# Carolo_schaltplan.net
KiCad netlist of a schematic drawn in EAGLE
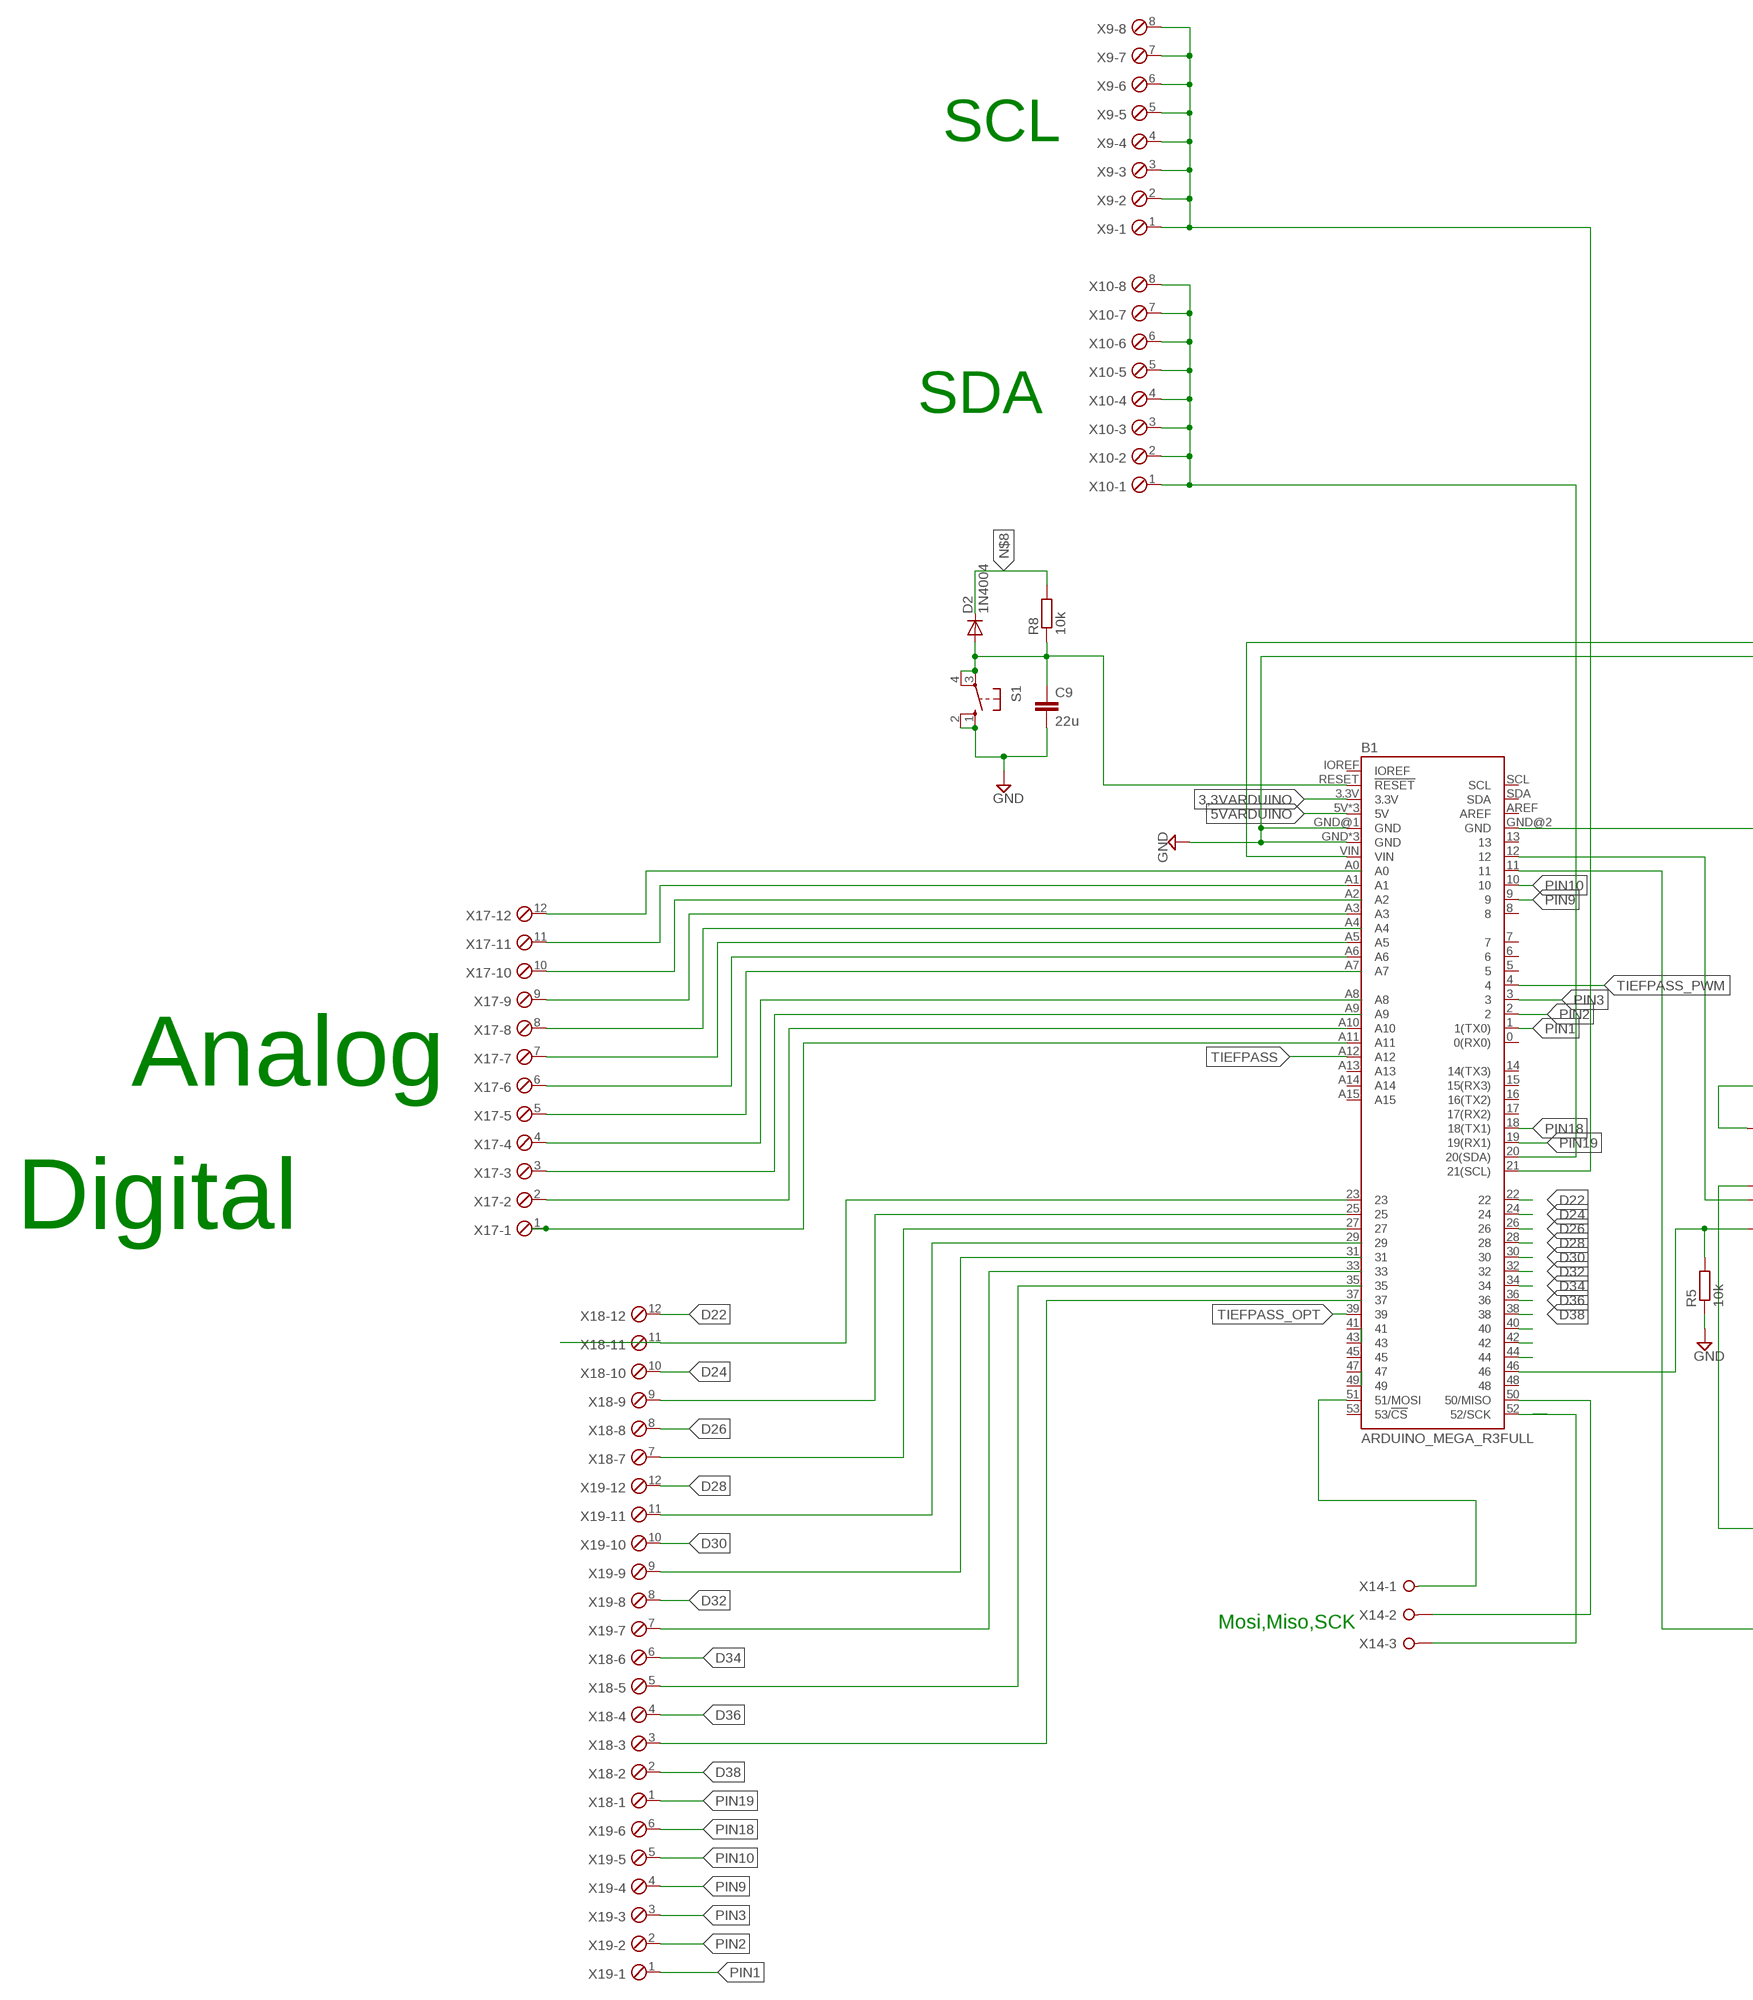
[diagram p0: schematic, sheet 1, part 1 of 2]
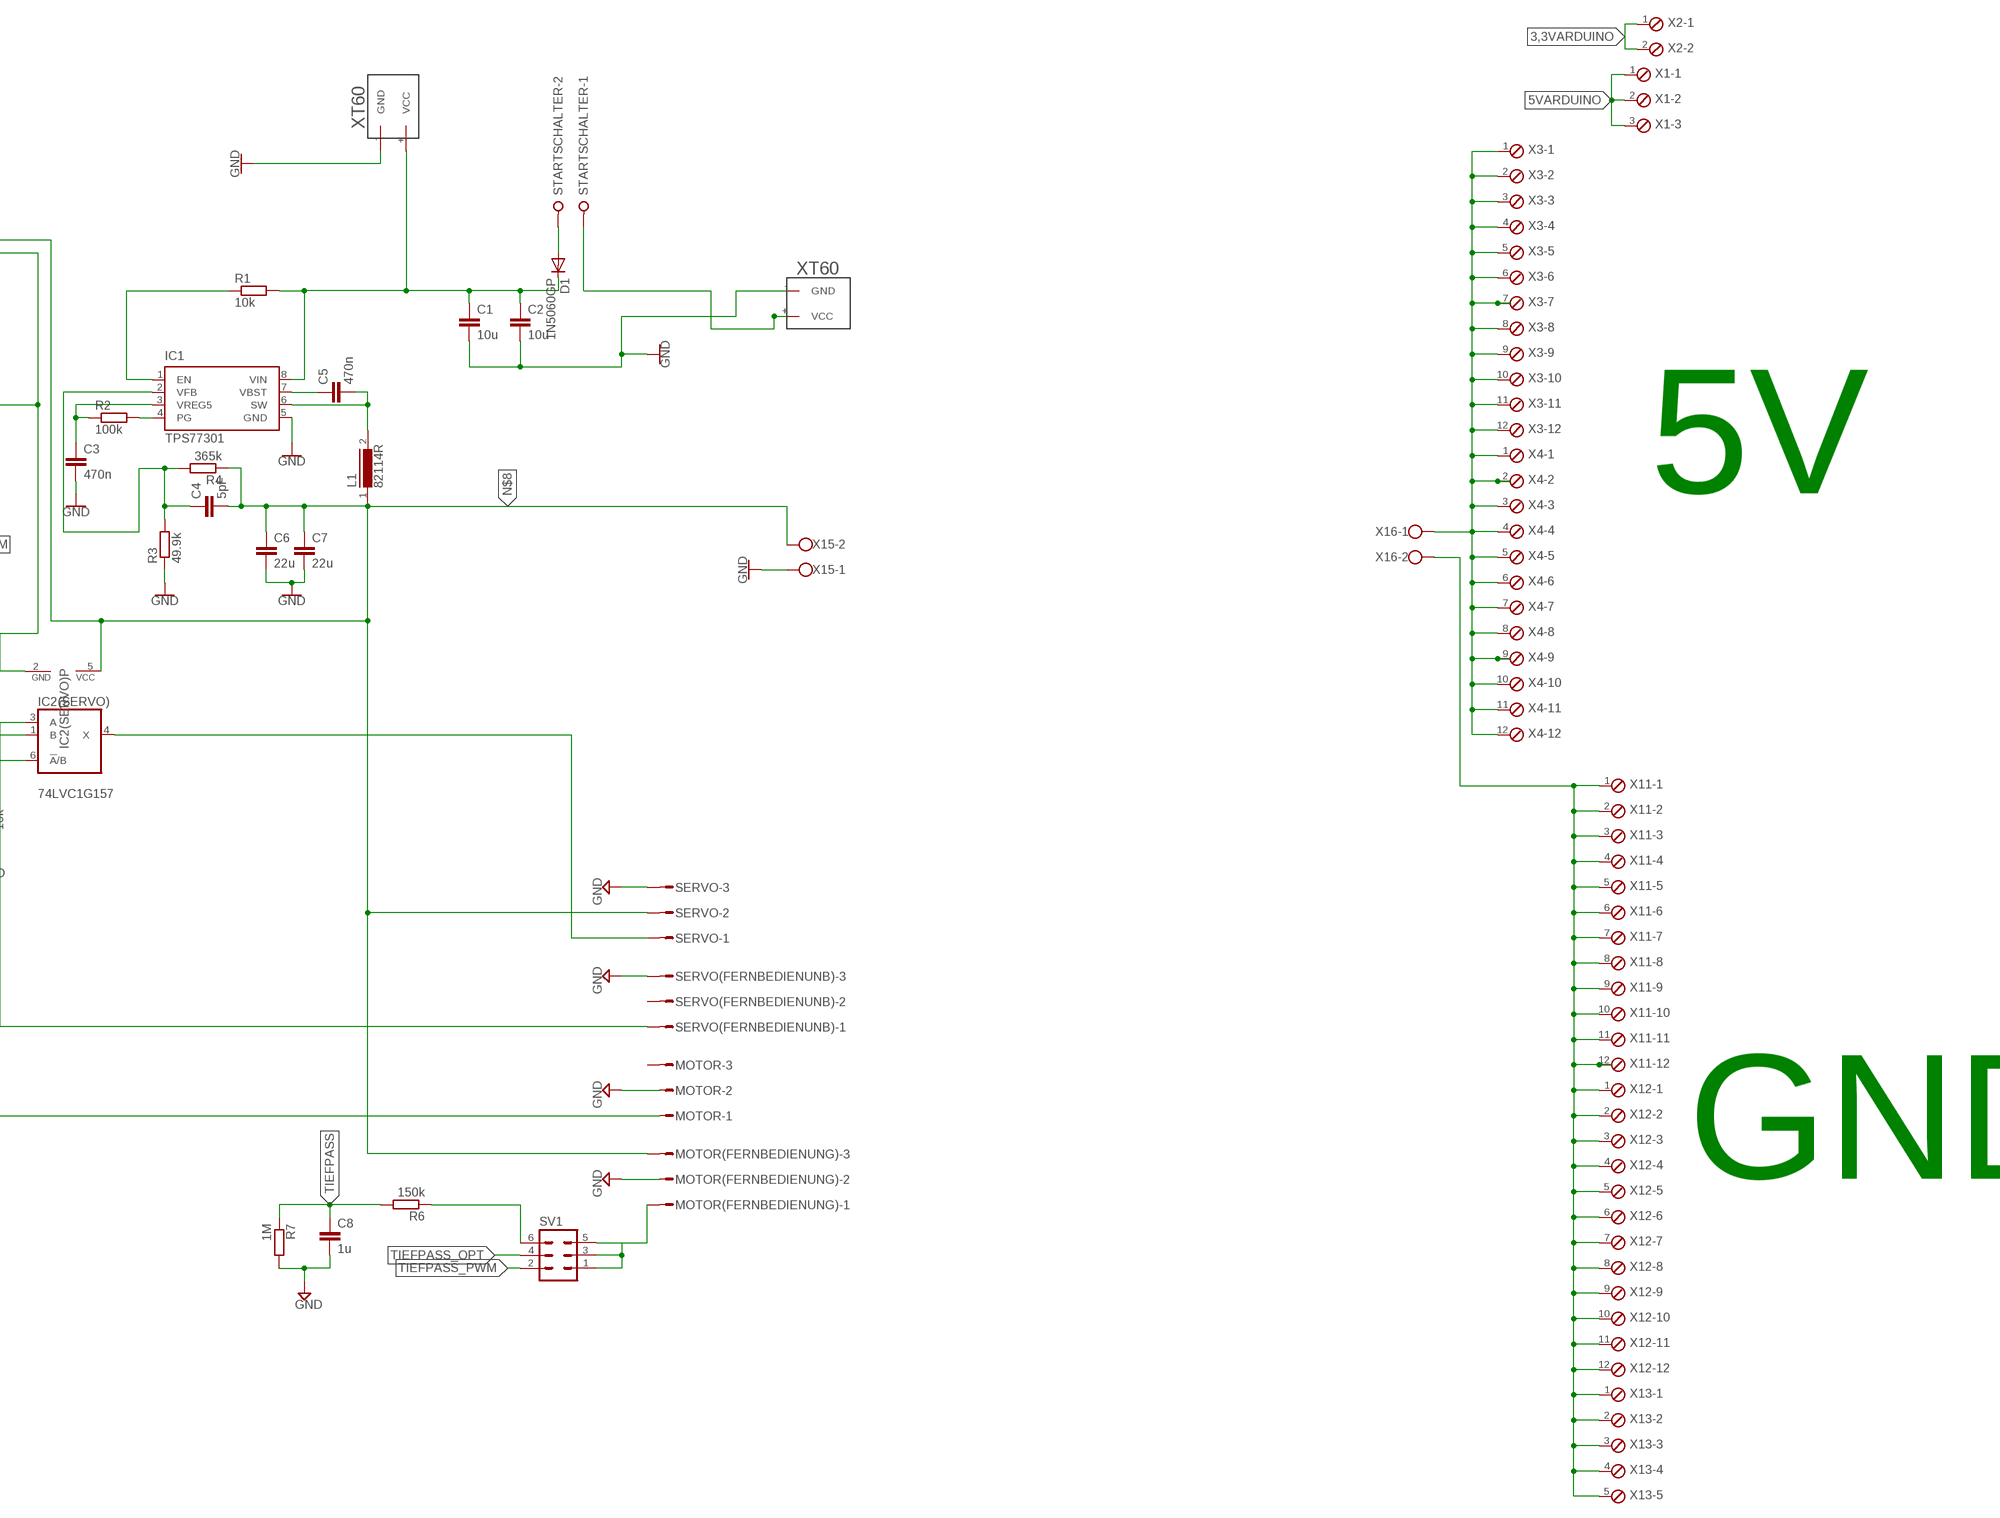
[diagram p1: schematic, sheet 1, part 2 of 2]

(export (version "E")
  (design (tool "Eeschema 10.0.6"))
  (components
    (comp (ref "B1")
      (value "ARDUINO_MEGA_R3FULL")
      (footprint "eagle-import:ARDUINO_MEGA_NO_SILK")
      (libsource (lib "eagle-import") (part "ARDUINO_MEGA_R3FULL"))
    )
    (comp (ref "C1")
      (value "10u")
      (footprint "eagle-import:C5B2.5")
      (libsource (lib "eagle-import") (part "C5/2.5"))
    )
    (comp (ref "C2")
      (value "10u")
      (footprint "eagle-import:C5B2.5")
      (libsource (lib "eagle-import") (part "C5/2.5"))
    )
    (comp (ref "C3")
      (value "470n")
      (footprint "eagle-import:C5B2.5")
      (libsource (lib "eagle-import") (part "C5/2.5"))
    )
    (comp (ref "C4")
      (value "5pF")
      (footprint "eagle-import:C5B2.5")
      (libsource (lib "eagle-import") (part "C5/2.5"))
    )
    (comp (ref "C5")
      (value "470n")
      (footprint "eagle-import:C5B2.5")
      (libsource (lib "eagle-import") (part "C5/2.5"))
    )
    (comp (ref "C6")
      (value "22u")
      (footprint "eagle-import:C5B2.5")
      (libsource (lib "eagle-import") (part "C5/2.5"))
    )
    (comp (ref "C7")
      (value "22u")
      (footprint "eagle-import:C5B2.5")
      (libsource (lib "eagle-import") (part "C5/2.5"))
    )
    (comp (ref "C8")
      (value "1u")
      (footprint "eagle-import:C5B2.5")
      (libsource (lib "eagle-import") (part "C5/2.5"))
    )
    (comp (ref "C9")
      (value "22u")
      (footprint "eagle-import:C5B2.5")
      (libsource (lib "eagle-import") (part "C5/2.5"))
    )
    (comp (ref "D1")
      (value "1N5060GP")
      (footprint "eagle-import:DO15-12")
      (libsource (lib "eagle-import") (part "1N5060GP"))
    )
    (comp (ref "D2")
      (value "1N4004")
      (footprint "eagle-import:DO41-10")
      (libsource (lib "eagle-import") (part "1N4004"))
    )
    (comp (ref "IC1")
      (value "TPS77301")
      (footprint "eagle-import:SOP-08")
      (fields (field (name "MF") "TEXAS INSTRUMENT CONNECTORS") (field (name "MPN") "TPS77301DGK"))
      (libsource (lib "eagle-import") (part "TPS77301"))
    )
    (comp (ref "IC2(SERVO)")
      (value "74LVC1G157")
      (footprint "eagle-import:DBV_R-PDSO-G6")
      (libsource (lib "eagle-import") (part "741G3157DBVR"))
    )
    (comp (ref "L1")
      (value "82114R")
      (footprint "eagle-import:82114R")
      (libsource (lib "eagle-import") (part "82114R"))
    )
    (comp (ref "MOTOR")
      (value "L03P")
      (footprint "eagle-import:L03P")
      (libsource (lib "eagle-import") (part "L03P"))
    )
    (comp (ref "MOTOR(FERNBEDIENUNG)")
      (value "L03P")
      (footprint "eagle-import:L03P")
      (libsource (lib "eagle-import") (part "L03P"))
    )
    (comp (ref "R1")
      (value "10k")
      (footprint "eagle-import:0309_12")
      (libsource (lib "eagle-import") (part "R-EU_0309/12"))
    )
    (comp (ref "R2")
      (value "100k")
      (footprint "eagle-import:0309_12")
      (libsource (lib "eagle-import") (part "R-EU_0309/12"))
    )
    (comp (ref "R3")
      (value "49.9k")
      (footprint "eagle-import:0309_12")
      (libsource (lib "eagle-import") (part "R-EU_0309/12"))
    )
    (comp (ref "R4")
      (value "365k")
      (footprint "eagle-import:0309_12")
      (libsource (lib "eagle-import") (part "R-EU_0309/12"))
    )
    (comp (ref "R5")
      (value "10k")
      (footprint "eagle-import:0309_12")
      (libsource (lib "eagle-import") (part "R-EU_0309/12"))
    )
    (comp (ref "R6")
      (value "150k")
      (footprint "eagle-import:0309_12")
      (libsource (lib "eagle-import") (part "R-EU_0309/12"))
    )
    (comp (ref "R7")
      (value "1M")
      (footprint "eagle-import:0309_12")
      (libsource (lib "eagle-import") (part "R-EU_0309/12"))
    )
    (comp (ref "R8")
      (value "10k")
      (footprint "eagle-import:0309_12")
      (libsource (lib "eagle-import") (part "R-EU_0309/12"))
    )
    (comp (ref "S1")
      (value "10-XX")
      (footprint "eagle-import:B3F-10XX")
      (fields (field (name "MPN") "B3F-1000"))
      (libsource (lib "eagle-import") (part "10-XX"))
    )
    (comp (ref "SERVO")
      (value "L03P")
      (footprint "eagle-import:L03P")
      (libsource (lib "eagle-import") (part "L03P"))
    )
    (comp (ref "SERVO(FERNBEDIENUNB)")
      (value "L03P")
      (footprint "eagle-import:L03P")
      (libsource (lib "eagle-import") (part "L03P"))
    )
    (comp (ref "STARTSCHALTER")
      (value "W237-02P")
      (footprint "eagle-import:W237-132")
      (libsource (lib "eagle-import") (part "W237-02P"))
    )
    (comp (ref "SV1")
      (value "ML6")
      (footprint "eagle-import:ML6")
      (libsource (lib "eagle-import") (part "ML6"))
    )
    (comp (ref "U$1")
      (value "XT60")
      (footprint "eagle-import:XT60")
      (libsource (lib "eagle-import") (part "XT60"))
    )
    (comp (ref "U$2")
      (value "XT60")
      (footprint "eagle-import:XT60")
      (libsource (lib "eagle-import") (part "XT60"))
    )
    (comp (ref "X1")
      (value "MPT3")
      (footprint "eagle-import:3POL254")
      (libsource (lib "eagle-import") (part "MPT3"))
    )
    (comp (ref "X2")
      (value "MPT2")
      (footprint "eagle-import:2POL254")
      (libsource (lib "eagle-import") (part "MPT2"))
    )
    (comp (ref "X3")
      (value "MPT12")
      (footprint "eagle-import:12POL254")
      (libsource (lib "eagle-import") (part "MPT12"))
    )
    (comp (ref "X4")
      (value "MPT12")
      (footprint "eagle-import:12POL254")
      (libsource (lib "eagle-import") (part "MPT12"))
    )
    (comp (ref "X9")
      (value "MPT8")
      (footprint "eagle-import:8POL254")
      (libsource (lib "eagle-import") (part "MPT8"))
    )
    (comp (ref "X10")
      (value "MPT8")
      (footprint "eagle-import:8POL254")
      (libsource (lib "eagle-import") (part "MPT8"))
    )
    (comp (ref "X11")
      (value "MPT12")
      (footprint "eagle-import:12POL254")
      (libsource (lib "eagle-import") (part "MPT12"))
    )
    (comp (ref "X12")
      (value "MPT12")
      (footprint "eagle-import:12POL254")
      (libsource (lib "eagle-import") (part "MPT12"))
    )
    (comp (ref "X13")
      (value "MPT5")
      (footprint "eagle-import:5POL254")
      (libsource (lib "eagle-import") (part "MPT5"))
    )
    (comp (ref "X14")
      (value "W237-03P")
      (footprint "eagle-import:W237-133")
      (libsource (lib "eagle-import") (part "W237-03P"))
    )
    (comp (ref "X15")
      (value "W237-102")
      (footprint "eagle-import:W237-102")
      (fields (field (name "MPN") "237-102"))
      (libsource (lib "eagle-import") (part "W237-102"))
    )
    (comp (ref "X16")
      (value "W237-102")
      (footprint "eagle-import:W237-102")
      (fields (field (name "MPN") "237-102"))
      (libsource (lib "eagle-import") (part "W237-102"))
    )
    (comp (ref "X17")
      (value "MPT12")
      (footprint "eagle-import:12POL254")
      (libsource (lib "eagle-import") (part "MPT12"))
    )
    (comp (ref "X18")
      (value "MPT12")
      (footprint "eagle-import:12POL254")
      (libsource (lib "eagle-import") (part "MPT12"))
    )
    (comp (ref "X19")
      (value "MPT12")
      (footprint "eagle-import:12POL254")
      (libsource (lib "eagle-import") (part "MPT12"))
    )
  )
  (nets
    (net (code "1") (name "3,3VARDUINO") (class "Default")
      (node (ref "B1") (pin "3.3V") (pinfunction "3.3V_3.3V") (pintype "bidirectional"))
      (node (ref "X2") (pin "1") (pinfunction "1_1") (pintype "passive"))
      (node (ref "X2") (pin "2") (pinfunction "1_2") (pintype "passive"))
    )
    (net (code "2") (name "5VARDUINO") (class "Default")
      (node (ref "B1") (pin "5V") (pinfunction "5V_5V") (pintype "bidirectional"))
      (node (ref "B1") (pin "5V@1") (pinfunction "5V_5V@1") (pintype "bidirectional"))
      (node (ref "B1") (pin "5V@2") (pinfunction "5V_5V@2") (pintype "bidirectional"))
      (node (ref "X1") (pin "1") (pinfunction "1_1") (pintype "passive"))
      (node (ref "X1") (pin "2") (pinfunction "1_2") (pintype "passive"))
      (node (ref "X1") (pin "3") (pinfunction "1_3") (pintype "passive"))
    )
    (net (code "3") (name "D22") (class "Default")
      (node (ref "B1") (pin "22") (pinfunction "22_22") (pintype "bidirectional"))
      (node (ref "X18") (pin "12") (pinfunction "1_12") (pintype "passive"))
    )
    (net (code "4") (name "D24") (class "Default")
      (node (ref "B1") (pin "24") (pinfunction "24_24") (pintype "bidirectional"))
      (node (ref "X18") (pin "10") (pinfunction "1_10") (pintype "passive"))
    )
    (net (code "5") (name "D26") (class "Default")
      (node (ref "B1") (pin "26") (pinfunction "26_26") (pintype "bidirectional"))
      (node (ref "X18") (pin "8") (pinfunction "1_8") (pintype "passive"))
    )
    (net (code "6") (name "D28") (class "Default")
      (node (ref "B1") (pin "28") (pinfunction "28_28") (pintype "bidirectional"))
      (node (ref "X19") (pin "12") (pinfunction "1_12") (pintype "passive"))
    )
    (net (code "7") (name "D30") (class "Default")
      (node (ref "B1") (pin "30") (pinfunction "30_30") (pintype "bidirectional"))
      (node (ref "X19") (pin "10") (pinfunction "1_10") (pintype "passive"))
    )
    (net (code "8") (name "D32") (class "Default")
      (node (ref "B1") (pin "32") (pinfunction "32_32") (pintype "bidirectional"))
      (node (ref "X19") (pin "8") (pinfunction "1_8") (pintype "passive"))
    )
    (net (code "9") (name "D34") (class "Default")
      (node (ref "B1") (pin "34") (pinfunction "34_34") (pintype "bidirectional"))
      (node (ref "X18") (pin "6") (pinfunction "1_6") (pintype "passive"))
    )
    (net (code "10") (name "D36") (class "Default")
      (node (ref "B1") (pin "36") (pinfunction "36_36") (pintype "bidirectional"))
      (node (ref "X18") (pin "4") (pinfunction "1_4") (pintype "passive"))
    )
    (net (code "11") (name "D38") (class "Default")
      (node (ref "B1") (pin "38") (pinfunction "38_38") (pintype "bidirectional"))
      (node (ref "X18") (pin "2") (pinfunction "1_2") (pintype "passive"))
    )
    (net (code "12") (name "GND") (class "Default")
      (node (ref "B1") (pin "GND") (pinfunction "GND_GND") (pintype "bidirectional"))
      (node (ref "B1") (pin "GND@1") (pinfunction "GND_GND@1") (pintype "bidirectional"))
      (node (ref "B1") (pin "GND@2") (pinfunction "GND_GND@2") (pintype "bidirectional"))
      (node (ref "B1") (pin "GND@3") (pinfunction "GND_GND@3") (pintype "bidirectional"))
      (node (ref "B1") (pin "GND@4") (pinfunction "GND_GND@4") (pintype "bidirectional"))
      (node (ref "C1") (pin "2") (pinfunction "2_2") (pintype "passive"))
      (node (ref "C2") (pin "2") (pinfunction "2_2") (pintype "passive"))
      (node (ref "C3") (pin "2") (pinfunction "2_2") (pintype "passive"))
      (node (ref "C6") (pin "2") (pinfunction "2_2") (pintype "passive"))
      (node (ref "C7") (pin "2") (pinfunction "2_2") (pintype "passive"))
      (node (ref "C8") (pin "2") (pinfunction "2_2") (pintype "passive"))
      (node (ref "C9") (pin "2") (pinfunction "2_2") (pintype "passive"))
      (node (ref "IC1") (pin "5") (pinfunction "GND_5") (pintype "input"))
      (node (ref "IC2(SERVO)") (pin "2") (pinfunction "GND_2") (pintype "power_in"))
      (node (ref "R3") (pin "1") (pinfunction "1_1") (pintype "passive"))
      (node (ref "R5") (pin "1") (pinfunction "1_1") (pintype "passive"))
      (node (ref "R7") (pin "2") (pinfunction "2_2") (pintype "passive"))
      (node (ref "S1") (pin "1") (pinfunction "S_1") (pintype "passive"))
      (node (ref "S1") (pin "2") (pinfunction "S1_2") (pintype "passive"))
      (node (ref "SERVO") (pin "3") (pinfunction "S_3") (pintype "passive"))
      (node (ref "SERVO(FERNBEDIENUNB)") (pin "3") (pinfunction "S_3") (pintype "passive"))
      (node (ref "U$2") (pin "-") (pinfunction "GND_-") (pintype "bidirectional"))
      (node (ref "X15") (pin "1") (pinfunction "KL_1") (pintype "passive"))
    )
    (net (code "13") (name "N$8") (class "Default")
      (node (ref "B1") (pin "VIN") (pinfunction "VIN_VIN") (pintype "bidirectional"))
      (node (ref "C4") (pin "2") (pinfunction "2_2") (pintype "passive"))
      (node (ref "C6") (pin "1") (pinfunction "1_1") (pintype "passive"))
      (node (ref "C7") (pin "1") (pinfunction "1_1") (pintype "passive"))
      (node (ref "D2") (pin "C") (pinfunction "C_C") (pintype "passive"))
      (node (ref "IC2(SERVO)") (pin "5") (pinfunction "VCC_5") (pintype "power_in"))
      (node (ref "L1") (pin "1") (pinfunction "1_1") (pintype "passive"))
      (node (ref "MOTOR(FERNBEDIENUNG)") (pin "3") (pinfunction "S_3") (pintype "passive"))
      (node (ref "R4") (pin "1") (pinfunction "1_1") (pintype "passive"))
      (node (ref "R8") (pin "2") (pinfunction "2_2") (pintype "passive"))
      (node (ref "SERVO") (pin "2") (pinfunction "S_2") (pintype "passive"))
      (node (ref "X15") (pin "2") (pinfunction "KL_2") (pintype "passive"))
      (node (ref "X16") (pin "1") (pinfunction "KL_1") (pintype "passive"))
      (node (ref "X3") (pin "1") (pinfunction "1_1") (pintype "passive"))
      (node (ref "X3") (pin "10") (pinfunction "1_10") (pintype "passive"))
      (node (ref "X3") (pin "11") (pinfunction "1_11") (pintype "passive"))
      (node (ref "X3") (pin "12") (pinfunction "1_12") (pintype "passive"))
      (node (ref "X3") (pin "2") (pinfunction "1_2") (pintype "passive"))
      (node (ref "X3") (pin "3") (pinfunction "1_3") (pintype "passive"))
      (node (ref "X3") (pin "4") (pinfunction "1_4") (pintype "passive"))
      (node (ref "X3") (pin "5") (pinfunction "1_5") (pintype "passive"))
      (node (ref "X3") (pin "6") (pinfunction "1_6") (pintype "passive"))
      (node (ref "X3") (pin "7") (pinfunction "1_7") (pintype "passive"))
      (node (ref "X3") (pin "8") (pinfunction "1_8") (pintype "passive"))
      (node (ref "X3") (pin "9") (pinfunction "1_9") (pintype "passive"))
      (node (ref "X4") (pin "1") (pinfunction "1_1") (pintype "passive"))
      (node (ref "X4") (pin "10") (pinfunction "1_10") (pintype "passive"))
      (node (ref "X4") (pin "11") (pinfunction "1_11") (pintype "passive"))
      (node (ref "X4") (pin "12") (pinfunction "1_12") (pintype "passive"))
      (node (ref "X4") (pin "2") (pinfunction "1_2") (pintype "passive"))
      (node (ref "X4") (pin "3") (pinfunction "1_3") (pintype "passive"))
      (node (ref "X4") (pin "4") (pinfunction "1_4") (pintype "passive"))
      (node (ref "X4") (pin "5") (pinfunction "1_5") (pintype "passive"))
      (node (ref "X4") (pin "6") (pinfunction "1_6") (pintype "passive"))
      (node (ref "X4") (pin "7") (pinfunction "1_7") (pintype "passive"))
      (node (ref "X4") (pin "8") (pinfunction "1_8") (pintype "passive"))
      (node (ref "X4") (pin "9") (pinfunction "1_9") (pintype "passive"))
    )
    (net (code "14") (name "Net-(B1-20(SDA))") (class "Default")
      (node (ref "B1") (pin "20") (pinfunction "20(SDA)_20") (pintype "bidirectional"))
      (node (ref "X10") (pin "1") (pinfunction "1_1") (pintype "passive"))
      (node (ref "X10") (pin "2") (pinfunction "1_2") (pintype "passive"))
      (node (ref "X10") (pin "3") (pinfunction "1_3") (pintype "passive"))
      (node (ref "X10") (pin "4") (pinfunction "1_4") (pintype "passive"))
      (node (ref "X10") (pin "5") (pinfunction "1_5") (pintype "passive"))
      (node (ref "X10") (pin "6") (pinfunction "1_6") (pintype "passive"))
      (node (ref "X10") (pin "7") (pinfunction "1_7") (pintype "passive"))
      (node (ref "X10") (pin "8") (pinfunction "1_8") (pintype "passive"))
    )
    (net (code "15") (name "Net-(B1-21(SCL))") (class "Default")
      (node (ref "B1") (pin "21") (pinfunction "21(SCL)_21") (pintype "bidirectional"))
      (node (ref "X9") (pin "1") (pinfunction "1_1") (pintype "passive"))
      (node (ref "X9") (pin "2") (pinfunction "1_2") (pintype "passive"))
      (node (ref "X9") (pin "3") (pinfunction "1_3") (pintype "passive"))
      (node (ref "X9") (pin "4") (pinfunction "1_4") (pintype "passive"))
      (node (ref "X9") (pin "5") (pinfunction "1_5") (pintype "passive"))
      (node (ref "X9") (pin "6") (pinfunction "1_6") (pintype "passive"))
      (node (ref "X9") (pin "7") (pinfunction "1_7") (pintype "passive"))
      (node (ref "X9") (pin "8") (pinfunction "1_8") (pintype "passive"))
    )
    (net (code "16") (name "Net-(B1-50{slash}MISO)") (class "Default")
      (node (ref "B1") (pin "50") (pinfunction "50/MISO_50") (pintype "bidirectional"))
      (node (ref "X14") (pin "2") (pinfunction "KL_2") (pintype "passive"))
    )
    (net (code "17") (name "Net-(B1-52{slash}SCK)") (class "Default")
      (node (ref "B1") (pin "52") (pinfunction "52/SCK_52") (pintype "bidirectional"))
      (node (ref "X14") (pin "3") (pinfunction "KL_3") (pintype "passive"))
    )
    (net (code "18") (name "Net-(B1-PadA11)") (class "Default")
      (node (ref "B1") (pin "A11") (pinfunction "A11_A11") (pintype "bidirectional"))
      (node (ref "X17") (pin "1") (pinfunction "1_1") (pintype "passive"))
    )
    (net (code "19") (name "Net-(B1-~{RESET})") (class "Default")
      (node (ref "B1") (pin "RESET") (pinfunction "~{RESET}_RESET") (pintype "bidirectional"))
      (node (ref "C9") (pin "1") (pinfunction "1_1") (pintype "passive"))
      (node (ref "D2") (pin "A") (pinfunction "A_A") (pintype "passive"))
      (node (ref "R8") (pin "1") (pinfunction "1_1") (pintype "passive"))
      (node (ref "S1") (pin "3") (pinfunction "P_3") (pintype "passive"))
      (node (ref "S1") (pin "4") (pinfunction "P1_4") (pintype "passive"))
    )
    (net (code "20") (name "Net-(IC1-EN)") (class "Default")
      (node (ref "IC1") (pin "1") (pinfunction "EN_1") (pintype "input"))
      (node (ref "R1") (pin "1") (pinfunction "1_1") (pintype "passive"))
    )
    (net (code "21") (name "Net-(IC1-PG)") (class "Default")
      (node (ref "IC1") (pin "4") (pinfunction "PG_4") (pintype "power_in"))
      (node (ref "R2") (pin "2") (pinfunction "2_2") (pintype "passive"))
    )
    (net (code "22") (name "Net-(IC1-SW)") (class "Default")
      (node (ref "C5") (pin "2") (pinfunction "2_2") (pintype "passive"))
      (node (ref "IC1") (pin "6") (pinfunction "SW_6") (pintype "input"))
      (node (ref "L1") (pin "2") (pinfunction "2_2") (pintype "passive"))
    )
    (net (code "23") (name "Net-(IC1-VBST)") (class "Default")
      (node (ref "C5") (pin "1") (pinfunction "1_1") (pintype "passive"))
      (node (ref "IC1") (pin "7") (pinfunction "VBST_7") (pintype "output"))
    )
    (net (code "24") (name "Net-(IC1-VFB)") (class "Default")
      (node (ref "C4") (pin "1") (pinfunction "1_1") (pintype "passive"))
      (node (ref "IC1") (pin "2") (pinfunction "VFB_2") (pintype "input"))
      (node (ref "R3") (pin "2") (pinfunction "2_2") (pintype "passive"))
      (node (ref "R4") (pin "2") (pinfunction "2_2") (pintype "passive"))
    )
    (net (code "25") (name "Net-(IC1-VIN)") (class "Default")
      (node (ref "C1") (pin "1") (pinfunction "1_1") (pintype "passive"))
      (node (ref "C2") (pin "1") (pinfunction "1_1") (pintype "passive"))
      (node (ref "D1") (pin "C") (pinfunction "C_C") (pintype "passive"))
      (node (ref "IC1") (pin "8") (pinfunction "VIN_8") (pintype "passive"))
      (node (ref "R1") (pin "2") (pinfunction "2_2") (pintype "passive"))
      (node (ref "U$2") (pin "+") (pinfunction "VCC_+") (pintype "bidirectional"))
    )
    (net (code "26") (name "Net-(IC1-VREG5)") (class "Default")
      (node (ref "C3") (pin "1") (pinfunction "1_1") (pintype "passive"))
      (node (ref "IC1") (pin "3") (pinfunction "VREG5_3") (pintype "input"))
      (node (ref "R2") (pin "1") (pinfunction "1_1") (pintype "passive"))
    )
    (net (code "27") (name "Net-(IC2(SERVO)A-A)") (class "Default")
      (node (ref "IC2(SERVO)") (pin "3") (pinfunction "A_3") (pintype "bidirectional"))
      (node (ref "SERVO(FERNBEDIENUNB)") (pin "1") (pinfunction "S_1") (pintype "passive"))
    )
    (net (code "28") (name "Net-(IC2(SERVO)A-B)") (class "Default")
      (node (ref "B1") (pin "12") (pinfunction "12_12") (pintype "bidirectional"))
      (node (ref "IC2(SERVO)") (pin "1") (pinfunction "B_1") (pintype "bidirectional"))
    )
    (net (code "29") (name "Net-(IC2(SERVO)A-X)") (class "Default")
      (node (ref "IC2(SERVO)") (pin "4") (pinfunction "X_4") (pintype "bidirectional"))
      (node (ref "SERVO") (pin "1") (pinfunction "S_1") (pintype "passive"))
    )
    (net (code "30") (name "Net-(IC2(SERVO)A-~{A}{slash}B)") (class "Default")
      (node (ref "B1") (pin "46") (pinfunction "46_46") (pintype "bidirectional"))
      (node (ref "IC2(SERVO)") (pin "6") (pinfunction "~{A}/B_6") (pintype "input"))
      (node (ref "R5") (pin "2") (pinfunction "2_2") (pintype "passive"))
    )
    (net (code "31") (name "Net-(MOTOR(FERNBEDIENUNG)A-S)") (class "Default")
      (node (ref "MOTOR(FERNBEDIENUNG)") (pin "1") (pinfunction "S_1") (pintype "passive"))
      (node (ref "SV1") (pin "1") (pinfunction "1_1") (pintype "passive"))
      (node (ref "SV1") (pin "3") (pinfunction "3_3") (pintype "passive"))
      (node (ref "SV1") (pin "5") (pinfunction "5_5") (pintype "passive"))
    )
    (net (code "32") (name "Net-(R6-Pad1)") (class "Default")
      (node (ref "R6") (pin "1") (pinfunction "1_1") (pintype "passive"))
      (node (ref "SV1") (pin "6") (pinfunction "6_6") (pintype "passive"))
    )
    (net (code "33") (name "Net-(STARTSCHALTERA-KL)") (class "Default")
      (node (ref "STARTSCHALTER") (pin "1") (pinfunction "KL_1") (pintype "passive"))
      (node (ref "U$1") (pin "+") (pinfunction "VCC_+") (pintype "bidirectional"))
    )
    (net (code "34") (name "Net-(STARTSCHALTERB-KL)") (class "Default")
      (node (ref "D1") (pin "A") (pinfunction "A_A") (pintype "passive"))
      (node (ref "STARTSCHALTER") (pin "2") (pinfunction "KL_2") (pintype "passive"))
    )
    (net (code "35") (name "Net-(X11B-1)") (class "Default")
      (node (ref "X11") (pin "1") (pinfunction "1_1") (pintype "passive"))
      (node (ref "X11") (pin "10") (pinfunction "1_10") (pintype "passive"))
      (node (ref "X11") (pin "11") (pinfunction "1_11") (pintype "passive"))
      (node (ref "X11") (pin "12") (pinfunction "1_12") (pintype "passive"))
      (node (ref "X11") (pin "2") (pinfunction "1_2") (pintype "passive"))
      (node (ref "X11") (pin "3") (pinfunction "1_3") (pintype "passive"))
      (node (ref "X11") (pin "4") (pinfunction "1_4") (pintype "passive"))
      (node (ref "X11") (pin "5") (pinfunction "1_5") (pintype "passive"))
      (node (ref "X11") (pin "6") (pinfunction "1_6") (pintype "passive"))
      (node (ref "X11") (pin "7") (pinfunction "1_7") (pintype "passive"))
      (node (ref "X11") (pin "8") (pinfunction "1_8") (pintype "passive"))
      (node (ref "X11") (pin "9") (pinfunction "1_9") (pintype "passive"))
      (node (ref "X12") (pin "1") (pinfunction "1_1") (pintype "passive"))
      (node (ref "X12") (pin "10") (pinfunction "1_10") (pintype "passive"))
      (node (ref "X12") (pin "11") (pinfunction "1_11") (pintype "passive"))
      (node (ref "X12") (pin "12") (pinfunction "1_12") (pintype "passive"))
      (node (ref "X12") (pin "2") (pinfunction "1_2") (pintype "passive"))
      (node (ref "X12") (pin "3") (pinfunction "1_3") (pintype "passive"))
      (node (ref "X12") (pin "4") (pinfunction "1_4") (pintype "passive"))
      (node (ref "X12") (pin "5") (pinfunction "1_5") (pintype "passive"))
      (node (ref "X12") (pin "6") (pinfunction "1_6") (pintype "passive"))
      (node (ref "X12") (pin "7") (pinfunction "1_7") (pintype "passive"))
      (node (ref "X12") (pin "8") (pinfunction "1_8") (pintype "passive"))
      (node (ref "X12") (pin "9") (pinfunction "1_9") (pintype "passive"))
      (node (ref "X13") (pin "1") (pinfunction "1_1") (pintype "passive"))
      (node (ref "X13") (pin "2") (pinfunction "1_2") (pintype "passive"))
      (node (ref "X13") (pin "3") (pinfunction "1_3") (pintype "passive"))
      (node (ref "X13") (pin "4") (pinfunction "1_4") (pintype "passive"))
      (node (ref "X13") (pin "5") (pinfunction "1_5") (pintype "passive"))
      (node (ref "X16") (pin "2") (pinfunction "KL_2") (pintype "passive"))
    )
    (net (code "36") (name "Net-(X17C-1)") (class "Default")
      (node (ref "B1") (pin "A1") (pinfunction "A1_A1") (pintype "bidirectional"))
      (node (ref "X17") (pin "11") (pinfunction "1_11") (pintype "passive"))
    )
    (net (code "37") (name "Net-(X17E-1)") (class "Default")
      (node (ref "B1") (pin "A10") (pinfunction "A10_A10") (pintype "bidirectional"))
      (node (ref "X17") (pin "2") (pinfunction "1_2") (pintype "passive"))
    )
    (net (code "38") (name "Net-(X17I-1)") (class "Default")
      (node (ref "B1") (pin "A6") (pinfunction "A6_A6") (pintype "bidirectional"))
      (node (ref "X17") (pin "6") (pinfunction "1_6") (pintype "passive"))
    )
    (net (code "39") (name "Net-(X17J-1)") (class "Default")
      (node (ref "B1") (pin "A5") (pinfunction "A5_A5") (pintype "bidirectional"))
      (node (ref "X17") (pin "7") (pinfunction "1_7") (pintype "passive"))
    )
    (net (code "40") (name "Net-(X17L-1)") (class "Default")
      (node (ref "B1") (pin "A3") (pinfunction "A3_A3") (pintype "bidirectional"))
      (node (ref "X17") (pin "9") (pinfunction "1_9") (pintype "passive"))
    )
    (net (code "41") (name "Net-(X18C-1)") (class "Default")
      (node (ref "B1") (pin "23") (pinfunction "23_23") (pintype "bidirectional"))
      (node (ref "X18") (pin "11") (pinfunction "1_11") (pintype "passive"))
    )
    (net (code "42") (name "Net-(X18J-1)") (class "Default")
      (node (ref "B1") (pin "27") (pinfunction "27_27") (pintype "bidirectional"))
      (node (ref "X18") (pin "7") (pinfunction "1_7") (pintype "passive"))
    )
    (net (code "43") (name "Net-(X18L-1)") (class "Default")
      (node (ref "B1") (pin "25") (pinfunction "25_25") (pintype "bidirectional"))
      (node (ref "X18") (pin "9") (pinfunction "1_9") (pintype "passive"))
    )
    (net (code "44") (name "PIN1") (class "Default")
      (node (ref "B1") (pin "1") (pinfunction "1(TX0)_1") (pintype "bidirectional"))
      (node (ref "X19") (pin "1") (pinfunction "1_1") (pintype "passive"))
    )
    (net (code "45") (name "PIN2") (class "Default")
      (node (ref "B1") (pin "2") (pinfunction "2_2") (pintype "bidirectional"))
      (node (ref "X19") (pin "2") (pinfunction "1_2") (pintype "passive"))
    )
    (net (code "46") (name "PIN3") (class "Default")
      (node (ref "B1") (pin "3") (pinfunction "3_3") (pintype "bidirectional"))
      (node (ref "X19") (pin "3") (pinfunction "1_3") (pintype "passive"))
    )
    (net (code "47") (name "PIN9") (class "Default")
      (node (ref "B1") (pin "9") (pinfunction "9_9") (pintype "bidirectional"))
      (node (ref "X19") (pin "4") (pinfunction "1_4") (pintype "passive"))
    )
    (net (code "48") (name "PIN10") (class "Default")
      (node (ref "B1") (pin "10") (pinfunction "10_10") (pintype "bidirectional"))
      (node (ref "X19") (pin "5") (pinfunction "1_5") (pintype "passive"))
    )
    (net (code "49") (name "PIN18") (class "Default")
      (node (ref "B1") (pin "18") (pinfunction "18(TX1)_18") (pintype "bidirectional"))
      (node (ref "X19") (pin "6") (pinfunction "1_6") (pintype "passive"))
    )
    (net (code "50") (name "PIN19") (class "Default")
      (node (ref "B1") (pin "19") (pinfunction "19(RX1)_19") (pintype "bidirectional"))
      (node (ref "X18") (pin "1") (pinfunction "1_1") (pintype "passive"))
    )
    (net (code "51") (name "TIEFPASS") (class "Default")
      (node (ref "B1") (pin "A12") (pinfunction "A12_A12") (pintype "bidirectional"))
      (node (ref "C8") (pin "1") (pinfunction "1_1") (pintype "passive"))
      (node (ref "R6") (pin "2") (pinfunction "2_2") (pintype "passive"))
      (node (ref "R7") (pin "1") (pinfunction "1_1") (pintype "passive"))
    )
    (net (code "52") (name "TIEFPASS_OPT") (class "Default")
      (node (ref "B1") (pin "39") (pinfunction "39_39") (pintype "bidirectional"))
      (node (ref "SV1") (pin "4") (pinfunction "4_4") (pintype "passive"))
    )
    (net (code "53") (name "TIEFPASS_PWM") (class "Default")
      (node (ref "B1") (pin "4") (pinfunction "4_4") (pintype "bidirectional"))
      (node (ref "SV1") (pin "2") (pinfunction "2_2") (pintype "passive"))
    )
    (net (code "54") (name "unconnected-(B1-0(RX0)-Pad0)") (class "Default")
      (node (ref "B1") (pin "0") (pinfunction "0(RX0)_0") (pintype "bidirectional"))
    )
    (net (code "55") (name "unconnected-(B1-14(TX3)-Pad14)") (class "Default")
      (node (ref "B1") (pin "14") (pinfunction "14(TX3)_14") (pintype "bidirectional"))
    )
    (net (code "56") (name "unconnected-(B1-15(RX3)-Pad15)") (class "Default")
      (node (ref "B1") (pin "15") (pinfunction "15(RX3)_15") (pintype "bidirectional"))
    )
    (net (code "57") (name "unconnected-(B1-16(TX2)-Pad16)") (class "Default")
      (node (ref "B1") (pin "16") (pinfunction "16(TX2)_16") (pintype "bidirectional"))
    )
    (net (code "58") (name "unconnected-(B1-17(RX2)-Pad17)") (class "Default")
      (node (ref "B1") (pin "17") (pinfunction "17(RX2)_17") (pintype "bidirectional"))
    )
    (net (code "59") (name "unconnected-(B1-51{slash}MOSI-Pad51)") (class "Default")
      (node (ref "B1") (pin "51") (pinfunction "51/MOSI_51") (pintype "bidirectional"))
    )
    (net (code "60") (name "unconnected-(B1-53{slash}~{CS}-Pad53)") (class "Default")
      (node (ref "B1") (pin "53") (pinfunction "53/~{CS}_53") (pintype "bidirectional"))
    )
    (net (code "61") (name "unconnected-(B1-Pad5)") (class "Default")
      (node (ref "B1") (pin "5") (pinfunction "5_5") (pintype "bidirectional"))
    )
    (net (code "62") (name "unconnected-(B1-Pad6)") (class "Default")
      (node (ref "B1") (pin "6") (pinfunction "6_6") (pintype "bidirectional"))
    )
    (net (code "63") (name "unconnected-(B1-Pad7)") (class "Default")
      (node (ref "B1") (pin "7") (pinfunction "7_7") (pintype "bidirectional"))
    )
    (net (code "64") (name "unconnected-(B1-Pad8)") (class "Default")
      (node (ref "B1") (pin "8") (pinfunction "8_8") (pintype "bidirectional"))
    )
    (net (code "65") (name "unconnected-(B1-Pad11)") (class "Default")
      (node (ref "B1") (pin "11") (pinfunction "11_11") (pintype "bidirectional"))
    )
    (net (code "66") (name "unconnected-(B1-Pad13)") (class "Default")
      (node (ref "B1") (pin "13") (pinfunction "13_13") (pintype "bidirectional"))
    )
    (net (code "67") (name "unconnected-(B1-Pad29)") (class "Default")
      (node (ref "B1") (pin "29") (pinfunction "29_29") (pintype "bidirectional"))
    )
    (net (code "68") (name "unconnected-(B1-Pad31)") (class "Default")
      (node (ref "B1") (pin "31") (pinfunction "31_31") (pintype "bidirectional"))
    )
    (net (code "69") (name "unconnected-(B1-Pad33)") (class "Default")
      (node (ref "B1") (pin "33") (pinfunction "33_33") (pintype "bidirectional"))
    )
    (net (code "70") (name "unconnected-(B1-Pad35)") (class "Default")
      (node (ref "B1") (pin "35") (pinfunction "35_35") (pintype "bidirectional"))
    )
    (net (code "71") (name "unconnected-(B1-Pad37)") (class "Default")
      (node (ref "B1") (pin "37") (pinfunction "37_37") (pintype "bidirectional"))
    )
    (net (code "72") (name "unconnected-(B1-Pad40)") (class "Default")
      (node (ref "B1") (pin "40") (pinfunction "40_40") (pintype "bidirectional"))
    )
    (net (code "73") (name "unconnected-(B1-Pad41)") (class "Default")
      (node (ref "B1") (pin "41") (pinfunction "41_41") (pintype "bidirectional"))
    )
    (net (code "74") (name "unconnected-(B1-Pad42)") (class "Default")
      (node (ref "B1") (pin "42") (pinfunction "42_42") (pintype "bidirectional"))
    )
    (net (code "75") (name "unconnected-(B1-Pad43)") (class "Default")
      (node (ref "B1") (pin "43") (pinfunction "43_43") (pintype "bidirectional"))
    )
    (net (code "76") (name "unconnected-(B1-Pad44)") (class "Default")
      (node (ref "B1") (pin "44") (pinfunction "44_44") (pintype "bidirectional"))
    )
    (net (code "77") (name "unconnected-(B1-Pad45)") (class "Default")
      (node (ref "B1") (pin "45") (pinfunction "45_45") (pintype "bidirectional"))
    )
    (net (code "78") (name "unconnected-(B1-Pad47)") (class "Default")
      (node (ref "B1") (pin "47") (pinfunction "47_47") (pintype "bidirectional"))
    )
    (net (code "79") (name "unconnected-(B1-Pad48)") (class "Default")
      (node (ref "B1") (pin "48") (pinfunction "48_48") (pintype "bidirectional"))
    )
    (net (code "80") (name "unconnected-(B1-Pad49)") (class "Default")
      (node (ref "B1") (pin "49") (pinfunction "49_49") (pintype "bidirectional"))
    )
    (net (code "81") (name "unconnected-(B1-PadA0)") (class "Default")
      (node (ref "B1") (pin "A0") (pinfunction "A0_A0") (pintype "bidirectional"))
    )
    (net (code "82") (name "unconnected-(B1-PadA2)") (class "Default")
      (node (ref "B1") (pin "A2") (pinfunction "A2_A2") (pintype "bidirectional"))
    )
    (net (code "83") (name "unconnected-(B1-PadA4)") (class "Default")
      (node (ref "B1") (pin "A4") (pinfunction "A4_A4") (pintype "bidirectional"))
    )
    (net (code "84") (name "unconnected-(B1-PadA7)") (class "Default")
      (node (ref "B1") (pin "A7") (pinfunction "A7_A7") (pintype "bidirectional"))
    )
    (net (code "85") (name "unconnected-(B1-PadA8)") (class "Default")
      (node (ref "B1") (pin "A8") (pinfunction "A8_A8") (pintype "bidirectional"))
    )
    (net (code "86") (name "unconnected-(B1-PadA9)") (class "Default")
      (node (ref "B1") (pin "A9") (pinfunction "A9_A9") (pintype "bidirectional"))
    )
    (net (code "87") (name "unconnected-(B1-PadA13)") (class "Default")
      (node (ref "B1") (pin "A13") (pinfunction "A13_A13") (pintype "bidirectional"))
    )
    (net (code "88") (name "unconnected-(B1-PadA14)") (class "Default")
      (node (ref "B1") (pin "A14") (pinfunction "A14_A14") (pintype "bidirectional"))
    )
    (net (code "89") (name "unconnected-(B1-PadA15)") (class "Default")
      (node (ref "B1") (pin "A15") (pinfunction "A15_A15") (pintype "bidirectional"))
    )
    (net (code "90") (name "unconnected-(B1-PadAREF)") (class "Default")
      (node (ref "B1") (pin "AREF") (pinfunction "AREF_AREF") (pintype "bidirectional"))
    )
    (net (code "91") (name "unconnected-(B1-PadIOREF)") (class "Default")
      (node (ref "B1") (pin "IOREF") (pinfunction "IOREF_IOREF") (pintype "bidirectional"))
    )
    (net (code "92") (name "unconnected-(B1-PadSCL)") (class "Default")
      (node (ref "B1") (pin "SCL") (pinfunction "SCL_SCL") (pintype "bidirectional"))
    )
    (net (code "93") (name "unconnected-(B1-PadSDA)") (class "Default")
      (node (ref "B1") (pin "SDA") (pinfunction "SDA_SDA") (pintype "bidirectional"))
    )
    (net (code "94") (name "unconnected-(MOTOR(FERNBEDIENUNG)B-S-Pad2)") (class "Default")
      (node (ref "MOTOR(FERNBEDIENUNG)") (pin "2") (pinfunction "S_2") (pintype "passive"))
    )
    (net (code "95") (name "unconnected-(MOTORA-S-Pad1)") (class "Default")
      (node (ref "MOTOR") (pin "1") (pinfunction "S_1") (pintype "passive"))
    )
    (net (code "96") (name "unconnected-(MOTORB-S-Pad2)") (class "Default")
      (node (ref "MOTOR") (pin "2") (pinfunction "S_2") (pintype "passive"))
    )
    (net (code "97") (name "unconnected-(MOTORC-S-Pad3)") (class "Default")
      (node (ref "MOTOR") (pin "3") (pinfunction "S_3") (pintype "passive"))
    )
    (net (code "98") (name "unconnected-(SERVO(FERNBEDIENUNB)B-S-Pad2)") (class "Default")
      (node (ref "SERVO(FERNBEDIENUNB)") (pin "2") (pinfunction "S_2") (pintype "passive"))
    )
    (net (code "99") (name "unconnected-(U$1-GND-Pad-)") (class "Default")
      (node (ref "U$1") (pin "-") (pinfunction "GND_-") (pintype "bidirectional"))
    )
    (net (code "100") (name "unconnected-(X14A-KL-Pad1)") (class "Default")
      (node (ref "X14") (pin "1") (pinfunction "KL_1") (pintype "passive"))
    )
    (net (code "101") (name "unconnected-(X17B-1-Pad10)") (class "Default")
      (node (ref "X17") (pin "10") (pinfunction "1_10") (pintype "passive"))
    )
    (net (code "102") (name "unconnected-(X17D-1-Pad12)") (class "Default")
      (node (ref "X17") (pin "12") (pinfunction "1_12") (pintype "passive"))
    )
    (net (code "103") (name "unconnected-(X17F-1-Pad3)") (class "Default")
      (node (ref "X17") (pin "3") (pinfunction "1_3") (pintype "passive"))
    )
    (net (code "104") (name "unconnected-(X17G-1-Pad4)") (class "Default")
      (node (ref "X17") (pin "4") (pinfunction "1_4") (pintype "passive"))
    )
    (net (code "105") (name "unconnected-(X17H-1-Pad5)") (class "Default")
      (node (ref "X17") (pin "5") (pinfunction "1_5") (pintype "passive"))
    )
    (net (code "106") (name "unconnected-(X17K-1-Pad8)") (class "Default")
      (node (ref "X17") (pin "8") (pinfunction "1_8") (pintype "passive"))
    )
    (net (code "107") (name "unconnected-(X18F-1-Pad3)") (class "Default")
      (node (ref "X18") (pin "3") (pinfunction "1_3") (pintype "passive"))
    )
    (net (code "108") (name "unconnected-(X18H-1-Pad5)") (class "Default")
      (node (ref "X18") (pin "5") (pinfunction "1_5") (pintype "passive"))
    )
    (net (code "109") (name "unconnected-(X19C-1-Pad11)") (class "Default")
      (node (ref "X19") (pin "11") (pinfunction "1_11") (pintype "passive"))
    )
    (net (code "110") (name "unconnected-(X19J-1-Pad7)") (class "Default")
      (node (ref "X19") (pin "7") (pinfunction "1_7") (pintype "passive"))
    )
    (net (code "111") (name "unconnected-(X19L-1-Pad9)") (class "Default")
      (node (ref "X19") (pin "9") (pinfunction "1_9") (pintype "passive"))
    )
  )
)
